# DummyLoad.net
KiCad netlist of a schematic drawn in EAGLE
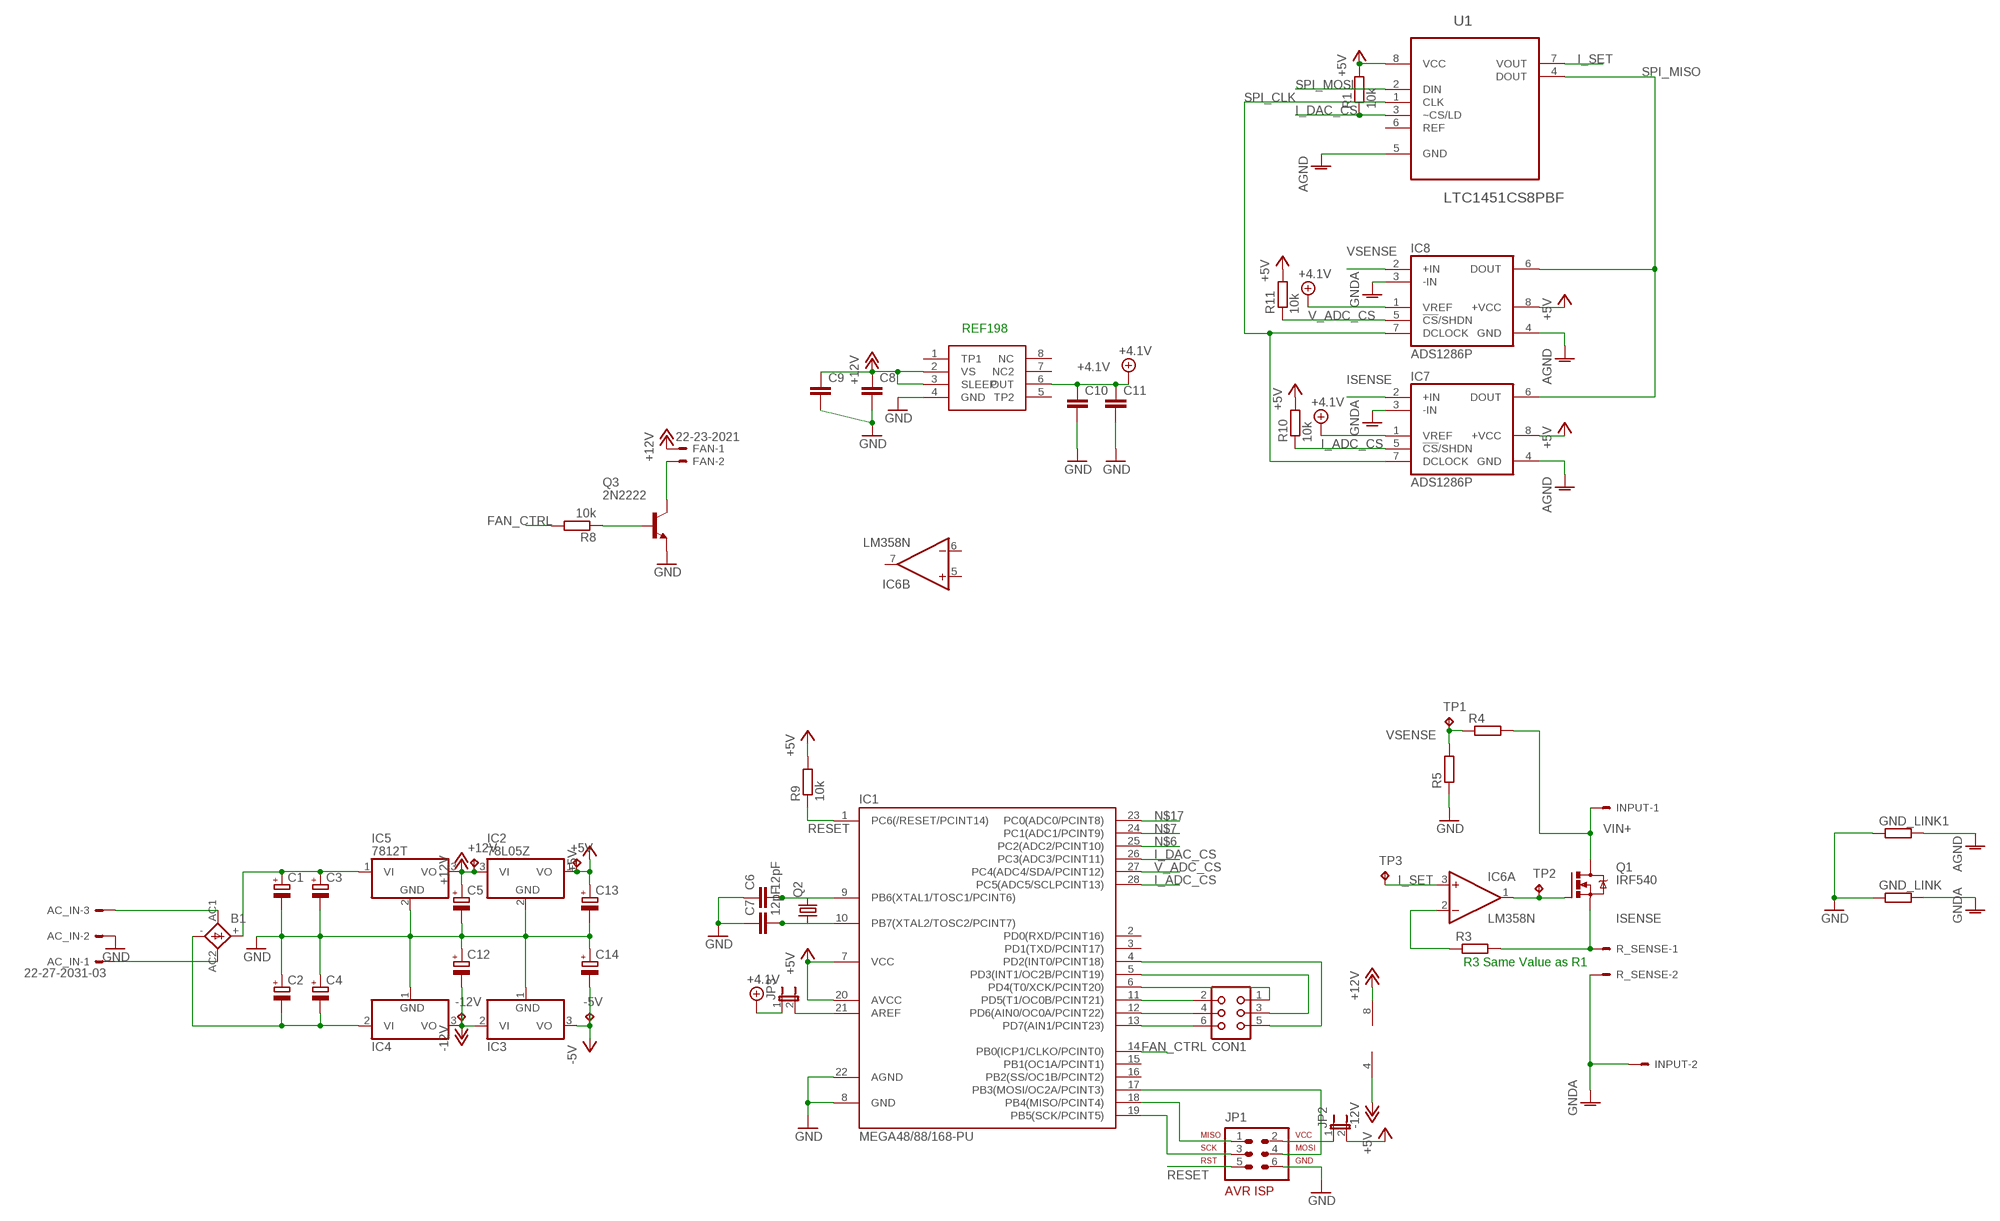
[diagram p0: schematic, sheet 1]

(export (version "E")
  (design (tool "Eeschema 10.0.6"))
  (components
    (comp (ref "+5V")
      (value "TPB2,54")
      (footprint "eagle-import:B2,54")
      (libsource (lib "eagle-import") (part "TPB2,54"))
    )
    (comp (ref "+12V")
      (value "TPB2,54")
      (footprint "eagle-import:B2,54")
      (libsource (lib "eagle-import") (part "TPB2,54"))
    )
    (comp (ref "-5V")
      (value "TPB2,54")
      (footprint "eagle-import:B2,54")
      (libsource (lib "eagle-import") (part "TPB2,54"))
    )
    (comp (ref "-12V")
      (value "TPB2,54")
      (footprint "eagle-import:B2,54")
      (libsource (lib "eagle-import") (part "TPB2,54"))
    )
    (comp (ref "AC_IN")
      (value "22-27-2031-03")
      (footprint "eagle-import:6410-03")
      (libsource (lib "eagle-import") (part "22-?-0327-2031"))
    )
    (comp (ref "B1")
      (value "2KBB-R")
      (footprint "eagle-import:2KBB-R")
      (libsource (lib "eagle-import") (part "2KBB-R"))
    )
    (comp (ref "C1")
      (value "CPOL-EUE5-8.5")
      (footprint "eagle-import:E5-8,5")
      (libsource (lib "eagle-import") (part "CPOL-EUE5-8.5"))
    )
    (comp (ref "C2")
      (value "CPOL-EUE5-8.5")
      (footprint "eagle-import:E5-8,5")
      (libsource (lib "eagle-import") (part "CPOL-EUE5-8.5"))
    )
    (comp (ref "C3")
      (value "CPOL-EUE5-8.5")
      (footprint "eagle-import:E5-8,5")
      (libsource (lib "eagle-import") (part "CPOL-EUE5-8.5"))
    )
    (comp (ref "C4")
      (value "CPOL-EUE5-8.5")
      (footprint "eagle-import:E5-8,5")
      (libsource (lib "eagle-import") (part "CPOL-EUE5-8.5"))
    )
    (comp (ref "C5")
      (value "CPOL-EUE2,5-6E")
      (footprint "eagle-import:E2,5-6E")
      (libsource (lib "eagle-import") (part "CPOL-EUE2,5-6E"))
    )
    (comp (ref "C6")
      (value "12pF")
      (footprint "eagle-import:C1206K")
      (libsource (lib "eagle-import") (part "C-EUC1206K"))
    )
    (comp (ref "C7")
      (value "12pF")
      (footprint "eagle-import:C1206K")
      (libsource (lib "eagle-import") (part "C-EUC1206K"))
    )
    (comp (ref "C8")
      (value "C-EUC1206K")
      (footprint "eagle-import:C1206K")
      (libsource (lib "eagle-import") (part "C-EUC1206K"))
    )
    (comp (ref "C9")
      (value "C-EUC1206K")
      (footprint "eagle-import:C1206K")
      (libsource (lib "eagle-import") (part "C-EUC1206K"))
    )
    (comp (ref "C10")
      (value "C-EUC1206K")
      (footprint "eagle-import:C1206K")
      (libsource (lib "eagle-import") (part "C-EUC1206K"))
    )
    (comp (ref "C11")
      (value "C-EUC1206K")
      (footprint "eagle-import:C1206K")
      (libsource (lib "eagle-import") (part "C-EUC1206K"))
    )
    (comp (ref "C12")
      (value "CPOL-EUE2,5-6E")
      (footprint "eagle-import:E2,5-6E")
      (libsource (lib "eagle-import") (part "CPOL-EUE2,5-6E"))
    )
    (comp (ref "C13")
      (value "CPOL-EUE2,5-6E")
      (footprint "eagle-import:E2,5-6E")
      (libsource (lib "eagle-import") (part "CPOL-EUE2,5-6E"))
    )
    (comp (ref "C14")
      (value "CPOL-EUE2,5-6E")
      (footprint "eagle-import:E2,5-6E")
      (libsource (lib "eagle-import") (part "CPOL-EUE2,5-6E"))
    )
    (comp (ref "CON1")
      (value "CON06")
      (footprint "eagle-import:CON06")
      (libsource (lib "eagle-import") (part "CON06"))
    )
    (comp (ref "FAN")
      (value "22-23-2021")
      (footprint "eagle-import:22-23-2021")
      (fields (field (name "MF") "MOLEX"))
      (libsource (lib "eagle-import") (part "22-23-2021"))
    )
    (comp (ref "GND_LINK")
      (value "R-EU_0204/2V")
      (footprint "eagle-import:0204V")
      (libsource (lib "eagle-import") (part "R-EU_0204/2V"))
    )
    (comp (ref "GND_LINK1")
      (value "R-EU_0204/2V")
      (footprint "eagle-import:0204V")
      (libsource (lib "eagle-import") (part "R-EU_0204/2V"))
    )
    (comp (ref "IC1")
      (value "MEGA48/88/168-PU")
      (footprint "eagle-import:DIL28-3")
      (libsource (lib "eagle-import") (part "MEGA48/88/168-PU"))
    )
    (comp (ref "IC2")
      (value "78L05Z")
      (footprint "eagle-import:TO92")
      (libsource (lib "eagle-import") (part "78ZL05"))
    )
    (comp (ref "IC3")
      (value "79L05Z")
      (footprint "eagle-import:TO92")
      (libsource (lib "eagle-import") (part "79ZL05"))
    )
    (comp (ref "IC4")
      (value "7912T")
      (footprint "eagle-import:TO220H")
      (libsource (lib "eagle-import") (part "79T12"))
    )
    (comp (ref "IC5")
      (value "7812T")
      (footprint "eagle-import:TO220H")
      (libsource (lib "eagle-import") (part "78T12"))
    )
    (comp (ref "IC6")
      (value "LM358N")
      (footprint "eagle-import:DIL08")
      (libsource (lib "eagle-import") (part "LM358N"))
    )
    (comp (ref "IC7")
      (value "ADS1286P")
      (footprint "eagle-import:DIL08")
      (fields (field (name "MF") "TEXAS INSTRUMENT CONNECTORS"))
      (libsource (lib "eagle-import") (part "ADS1286P"))
    )
    (comp (ref "IC8")
      (value "ADS1286P")
      (footprint "eagle-import:DIL08")
      (fields (field (name "MF") "TEXAS INSTRUMENT CONNECTORS"))
      (libsource (lib "eagle-import") (part "ADS1286P"))
    )
    (comp (ref "INPUT")
      (value "KK-156-2")
      (footprint "eagle-import:KK-156-2")
      (libsource (lib "eagle-import") (part "KK-156-2"))
    )
    (comp (ref "JP1")
      (value "AVR-ISP-6VERT")
      (footprint "eagle-import:AVR-ISP-6")
      (libsource (lib "eagle-import") (part "AVR-ISP-6VERT"))
    )
    (comp (ref "JP2")
      (value "JP1E")
      (footprint "eagle-import:JP1")
      (libsource (lib "eagle-import") (part "JP1E"))
    )
    (comp (ref "JP3")
      (value "JP1E")
      (footprint "eagle-import:JP1")
      (libsource (lib "eagle-import") (part "JP1E"))
    )
    (comp (ref "Q1")
      (value "IRF540")
      (footprint "eagle-import:TO220BV")
      (libsource (lib "eagle-import") (part "IRF540"))
    )
    (comp (ref "Q2")
      (value "CRYSTALHC18U-V")
      (footprint "eagle-import:HC18U-V")
      (libsource (lib "eagle-import") (part "CRYSTALHC18U-V"))
    )
    (comp (ref "Q3")
      (value "2N2222")
      (footprint "eagle-import:TO18")
      (libsource (lib "eagle-import") (part "2N2222"))
    )
    (comp (ref "R1")
      (value "10k")
      (footprint "eagle-import:M1206")
      (libsource (lib "eagle-import") (part "R-EU_M1206"))
    )
    (comp (ref "R3")
      (value "R-EU_M1206")
      (footprint "eagle-import:M1206")
      (libsource (lib "eagle-import") (part "R-EU_M1206"))
    )
    (comp (ref "R4")
      (value "R-EU_M1206")
      (footprint "eagle-import:M1206")
      (libsource (lib "eagle-import") (part "R-EU_M1206"))
    )
    (comp (ref "R5")
      (value "R-EU_M1206")
      (footprint "eagle-import:M1206")
      (libsource (lib "eagle-import") (part "R-EU_M1206"))
    )
    (comp (ref "R8")
      (value "10k")
      (footprint "eagle-import:0204_7")
      (libsource (lib "eagle-import") (part "R-EU_0204/7"))
    )
    (comp (ref "R9")
      (value "10k")
      (footprint "eagle-import:M1206")
      (libsource (lib "eagle-import") (part "R-EU_M1206"))
    )
    (comp (ref "R10")
      (value "10k")
      (footprint "eagle-import:M1206")
      (libsource (lib "eagle-import") (part "R-EU_M1206"))
    )
    (comp (ref "R11")
      (value "10k")
      (footprint "eagle-import:M1206")
      (libsource (lib "eagle-import") (part "R-EU_M1206"))
    )
    (comp (ref "R_SENSE")
      (value "KK-156-2")
      (footprint "eagle-import:KK-156-2")
      (libsource (lib "eagle-import") (part "KK-156-2"))
    )
    (comp (ref "TP1")
      (value "TPB2,54")
      (footprint "eagle-import:B2,54")
      (libsource (lib "eagle-import") (part "TPB2,54"))
    )
    (comp (ref "TP2")
      (value "TPB2,54")
      (footprint "eagle-import:B2,54")
      (libsource (lib "eagle-import") (part "TPB2,54"))
    )
    (comp (ref "TP3")
      (value "TPB2,54")
      (footprint "eagle-import:B2,54")
      (libsource (lib "eagle-import") (part "TPB2,54"))
    )
    (comp (ref "U$1")
      (value "REF195")
      (footprint "eagle-import:DIL08")
      (libsource (lib "eagle-import") (part "REF195"))
    )
    (comp (ref "U1")
      (value "LTC1451CS8PBF")
      (footprint "eagle-import:SOIC127P600X175-8N")
      (fields (field (name "MPN") "LTC1451CS8#PBF"))
      (libsource (lib "eagle-import") (part "LTC1451CS8PBF"))
    )
  )
  (nets
    (net (code "1") (name "+4.1V") (class "Default")
      (node (ref "C10") (pin "1") (pinfunction "1_1") (pintype "passive"))
      (node (ref "C11") (pin "1") (pinfunction "1_1") (pintype "passive"))
      (node (ref "IC7") (pin "1") (pinfunction "VREF_1") (pintype "input"))
      (node (ref "IC8") (pin "1") (pinfunction "VREF_1") (pintype "input"))
      (node (ref "JP3") (pin "1") (pinfunction "1_1") (pintype "passive"))
      (node (ref "U$1") (pin "6") (pinfunction "OUT_6") (pintype "bidirectional"))
    )
    (net (code "2") (name "+5V") (class "Default")
      (node (ref "+5V") (pin "TP") (pinfunction "TP_TP") (pintype "input"))
      (node (ref "C13") (pin "+") (pinfunction "+_+") (pintype "passive"))
      (node (ref "IC1") (pin "20") (pinfunction "AVCC_20") (pintype "passive"))
      (node (ref "IC1") (pin "7") (pinfunction "VCC_7") (pintype "power_in"))
      (node (ref "IC2") (pin "1") (pinfunction "VO_1") (pintype "passive"))
      (node (ref "IC7") (pin "8") (pinfunction "+VCC_8") (pintype "power_in"))
      (node (ref "IC8") (pin "8") (pinfunction "+VCC_8") (pintype "power_in"))
      (node (ref "JP2") (pin "2") (pinfunction "2_2") (pintype "passive"))
      (node (ref "R1") (pin "2") (pinfunction "2_2") (pintype "passive"))
      (node (ref "R10") (pin "2") (pinfunction "2_2") (pintype "passive"))
      (node (ref "R11") (pin "2") (pinfunction "2_2") (pintype "passive"))
      (node (ref "R9") (pin "2") (pinfunction "2_2") (pintype "passive"))
      (node (ref "U1") (pin "8") (pinfunction "VCC_8") (pintype "power_in"))
    )
    (net (code "3") (name "+12V") (class "Default")
      (node (ref "+12V") (pin "TP") (pinfunction "TP_TP") (pintype "input"))
      (node (ref "C5") (pin "+") (pinfunction "+_+") (pintype "passive"))
      (node (ref "C8") (pin "1") (pinfunction "1_1") (pintype "passive"))
      (node (ref "C9") (pin "1") (pinfunction "1_1") (pintype "passive"))
      (node (ref "FAN") (pin "1") (pinfunction "S_1") (pintype "passive"))
      (node (ref "IC2") (pin "3") (pinfunction "VI_3") (pintype "input"))
      (node (ref "IC5") (pin "3") (pinfunction "VO_3") (pintype "passive"))
      (node (ref "IC6") (pin "8") (pinfunction "V+_8") (pintype "power_in"))
      (node (ref "U$1") (pin "2") (pinfunction "VS_2") (pintype "power_in"))
      (node (ref "U$1") (pin "3") (pinfunction "SLEEP_3") (pintype "bidirectional"))
    )
    (net (code "4") (name "-5V") (class "Default")
      (node (ref "-5V") (pin "TP") (pinfunction "TP_TP") (pintype "input"))
      (node (ref "C14") (pin "-") (pinfunction "-_-") (pintype "passive"))
      (node (ref "IC3") (pin "3") (pinfunction "VO_3") (pintype "passive"))
    )
    (net (code "5") (name "-12V") (class "Default")
      (node (ref "-12V") (pin "TP") (pinfunction "TP_TP") (pintype "input"))
      (node (ref "C12") (pin "-") (pinfunction "-_-") (pintype "passive"))
      (node (ref "IC3") (pin "2") (pinfunction "VI_2") (pintype "input"))
      (node (ref "IC4") (pin "3") (pinfunction "VO_3") (pintype "passive"))
      (node (ref "IC6") (pin "4") (pinfunction "V-_4") (pintype "power_in"))
    )
    (net (code "6") (name "/FAN_CTRL") (class "Default")
      (node (ref "IC1") (pin "14") (pinfunction "PB0(ICP1/CLKO/PCINT0)_14") (pintype "bidirectional"))
      (node (ref "R8") (pin "2") (pinfunction "2_2") (pintype "passive"))
    )
    (net (code "7") (name "/ISENSE") (class "Default")
      (node (ref "IC7") (pin "2") (pinfunction "+IN_2") (pintype "input"))
      (node (ref "Q1") (pin "S") (pinfunction "S_S") (pintype "passive"))
      (node (ref "R3") (pin "2") (pinfunction "2_2") (pintype "passive"))
      (node (ref "R_SENSE") (pin "1") (pinfunction "S_1") (pintype "passive"))
    )
    (net (code "8") (name "/I_ADC_CS") (class "Default")
      (node (ref "IC1") (pin "28") (pinfunction "PC5(ADC5/SCLPCINT13)_28") (pintype "bidirectional"))
      (node (ref "IC7") (pin "5") (pinfunction "~{CS}/SHDN_5") (pintype "input"))
      (node (ref "R10") (pin "1") (pinfunction "1_1") (pintype "passive"))
    )
    (net (code "9") (name "/I_DAC_CS") (class "Default")
      (node (ref "IC1") (pin "26") (pinfunction "PC3(ADC3/PCINT11)_26") (pintype "bidirectional"))
      (node (ref "R1") (pin "1") (pinfunction "1_1") (pintype "passive"))
      (node (ref "U1") (pin "3") (pinfunction "~{CS/LD}_3") (pintype "input"))
    )
    (net (code "10") (name "/I_SET") (class "Default")
      (node (ref "IC6") (pin "3") (pinfunction "+IN_3") (pintype "input"))
      (node (ref "TP3") (pin "TP") (pinfunction "TP_TP") (pintype "input"))
      (node (ref "U1") (pin "7") (pinfunction "VOUT_7") (pintype "output"))
    )
    (net (code "11") (name "/N$6") (class "Default")
      (node (ref "IC1") (pin "25") (pinfunction "PC2(ADC2/PCINT10)_25") (pintype "bidirectional"))
    )
    (net (code "12") (name "/N$7") (class "Default")
      (node (ref "IC1") (pin "24") (pinfunction "PC1(ADC1/PCINT9)_24") (pintype "bidirectional"))
    )
    (net (code "13") (name "/N$17") (class "Default")
      (node (ref "IC1") (pin "23") (pinfunction "PC0(ADC0/PCINT8)_23") (pintype "bidirectional"))
    )
    (net (code "14") (name "/RESET") (class "Default")
      (node (ref "IC1") (pin "1") (pinfunction "PC6(/RESET/PCINT14)_1") (pintype "bidirectional"))
      (node (ref "JP1") (pin "5") (pinfunction "5_5") (pintype "passive"))
      (node (ref "R9") (pin "1") (pinfunction "1_1") (pintype "passive"))
    )
    (net (code "15") (name "/SPI_CLK") (class "Default")
      (node (ref "IC1") (pin "19") (pinfunction "PB5(SCK/PCINT5)_19") (pintype "bidirectional"))
      (node (ref "IC7") (pin "7") (pinfunction "DCLOCK_7") (pintype "input"))
      (node (ref "IC8") (pin "7") (pinfunction "DCLOCK_7") (pintype "input"))
      (node (ref "JP1") (pin "3") (pinfunction "3_3") (pintype "passive"))
      (node (ref "U1") (pin "1") (pinfunction "CLK_1") (pintype "input"))
    )
    (net (code "16") (name "/SPI_MISO") (class "Default")
      (node (ref "IC1") (pin "18") (pinfunction "PB4(MISO/PCINT4)_18") (pintype "bidirectional"))
      (node (ref "IC7") (pin "6") (pinfunction "DOUT_6") (pintype "output"))
      (node (ref "IC8") (pin "6") (pinfunction "DOUT_6") (pintype "output"))
      (node (ref "JP1") (pin "1") (pinfunction "1_1") (pintype "passive"))
      (node (ref "U1") (pin "4") (pinfunction "DOUT_4") (pintype "output"))
    )
    (net (code "17") (name "/SPI_MOSI") (class "Default")
      (node (ref "IC1") (pin "17") (pinfunction "PB3(MOSI/OC2A/PCINT3)_17") (pintype "bidirectional"))
      (node (ref "JP1") (pin "4") (pinfunction "4_4") (pintype "passive"))
      (node (ref "U1") (pin "2") (pinfunction "DIN_2") (pintype "input"))
    )
    (net (code "18") (name "/VIN+") (class "Default")
      (node (ref "INPUT") (pin "1") (pinfunction "S_1") (pintype "passive"))
      (node (ref "Q1") (pin "D") (pinfunction "D_D") (pintype "passive"))
      (node (ref "R4") (pin "2") (pinfunction "2_2") (pintype "passive"))
    )
    (net (code "19") (name "/VSENSE") (class "Default")
      (node (ref "IC8") (pin "2") (pinfunction "+IN_2") (pintype "input"))
      (node (ref "R4") (pin "1") (pinfunction "1_1") (pintype "passive"))
      (node (ref "R5") (pin "2") (pinfunction "2_2") (pintype "passive"))
      (node (ref "TP1") (pin "TP") (pinfunction "TP_TP") (pintype "input"))
    )
    (net (code "20") (name "/V_ADC_CS") (class "Default")
      (node (ref "IC1") (pin "27") (pinfunction "PC4(ADC4/SDA/PCINT12)_27") (pintype "bidirectional"))
      (node (ref "IC8") (pin "5") (pinfunction "~{CS}/SHDN_5") (pintype "input"))
      (node (ref "R11") (pin "1") (pinfunction "1_1") (pintype "passive"))
    )
    (net (code "21") (name "AGND") (class "Default")
      (node (ref "GND_LINK1") (pin "2") (pinfunction "2_2") (pintype "passive"))
      (node (ref "IC7") (pin "4") (pinfunction "GND_4") (pintype "power_in"))
      (node (ref "IC8") (pin "4") (pinfunction "GND_4") (pintype "power_in"))
      (node (ref "U1") (pin "5") (pinfunction "GND_5") (pintype "passive"))
    )
    (net (code "22") (name "GND") (class "Default")
      (node (ref "AC_IN") (pin "2") (pinfunction "S_2") (pintype "passive"))
      (node (ref "C1") (pin "-") (pinfunction "-_-") (pintype "passive"))
      (node (ref "C10") (pin "2") (pinfunction "2_2") (pintype "passive"))
      (node (ref "C11") (pin "2") (pinfunction "2_2") (pintype "passive"))
      (node (ref "C12") (pin "+") (pinfunction "+_+") (pintype "passive"))
      (node (ref "C13") (pin "-") (pinfunction "-_-") (pintype "passive"))
      (node (ref "C14") (pin "+") (pinfunction "+_+") (pintype "passive"))
      (node (ref "C2") (pin "+") (pinfunction "+_+") (pintype "passive"))
      (node (ref "C3") (pin "-") (pinfunction "-_-") (pintype "passive"))
      (node (ref "C4") (pin "+") (pinfunction "+_+") (pintype "passive"))
      (node (ref "C5") (pin "-") (pinfunction "-_-") (pintype "passive"))
      (node (ref "C6") (pin "1") (pinfunction "1_1") (pintype "passive"))
      (node (ref "C7") (pin "1") (pinfunction "1_1") (pintype "passive"))
      (node (ref "C8") (pin "2") (pinfunction "2_2") (pintype "passive"))
      (node (ref "C9") (pin "2") (pinfunction "2_2") (pintype "passive"))
      (node (ref "GND_LINK") (pin "1") (pinfunction "1_1") (pintype "passive"))
      (node (ref "GND_LINK1") (pin "1") (pinfunction "1_1") (pintype "passive"))
      (node (ref "IC1") (pin "22") (pinfunction "AGND_22") (pintype "power_in"))
      (node (ref "IC1") (pin "8") (pinfunction "GND_8") (pintype "power_in"))
      (node (ref "IC2") (pin "2") (pinfunction "GND_2") (pintype "passive"))
      (node (ref "IC3") (pin "1") (pinfunction "GND_1") (pintype "passive"))
      (node (ref "IC4") (pin "1") (pinfunction "GND_1") (pintype "passive"))
      (node (ref "IC5") (pin "2") (pinfunction "GND_2") (pintype "passive"))
      (node (ref "JP1") (pin "6") (pinfunction "6_6") (pintype "passive"))
      (node (ref "Q3") (pin "1") (pinfunction "E_1") (pintype "passive"))
      (node (ref "R5") (pin "1") (pinfunction "1_1") (pintype "passive"))
      (node (ref "U$1") (pin "4") (pinfunction "GND_4") (pintype "power_in"))
    )
    (net (code "23") (name "GNDA") (class "Default")
      (node (ref "GND_LINK") (pin "2") (pinfunction "2_2") (pintype "passive"))
      (node (ref "IC7") (pin "3") (pinfunction "-IN_3") (pintype "input"))
      (node (ref "IC8") (pin "3") (pinfunction "-IN_3") (pintype "input"))
      (node (ref "INPUT") (pin "2") (pinfunction "S_2") (pintype "passive"))
      (node (ref "R_SENSE") (pin "2") (pinfunction "S_2") (pintype "passive"))
    )
    (net (code "24") (name "Net-(AC_INA-S)") (class "Default")
      (node (ref "AC_IN") (pin "1") (pinfunction "S_1") (pintype "passive"))
      (node (ref "B1") (pin "AC2") (pinfunction "AC2_AC2") (pintype "passive"))
    )
    (net (code "25") (name "Net-(AC_INC-S)") (class "Default")
      (node (ref "AC_IN") (pin "3") (pinfunction "S_3") (pintype "passive"))
      (node (ref "B1") (pin "AC1") (pinfunction "AC1_AC1") (pintype "passive"))
    )
    (net (code "26") (name "Net-(FANB-S)") (class "Default")
      (node (ref "FAN") (pin "2") (pinfunction "S_2") (pintype "passive"))
      (node (ref "Q3") (pin "3") (pinfunction "C_3") (pintype "passive"))
    )
    (net (code "27") (name "Net-(IC1-AREF)") (class "Default")
      (node (ref "IC1") (pin "21") (pinfunction "AREF_21") (pintype "passive"))
      (node (ref "JP3") (pin "2") (pinfunction "2_2") (pintype "passive"))
    )
    (net (code "28") (name "Net-(IC1-PB6(XTAL1{slash}TOSC1{slash}PCINT6))") (class "Default")
      (node (ref "C6") (pin "2") (pinfunction "2_2") (pintype "passive"))
      (node (ref "IC1") (pin "9") (pinfunction "PB6(XTAL1/TOSC1/PCINT6)_9") (pintype "bidirectional"))
      (node (ref "Q2") (pin "2") (pinfunction "2_2") (pintype "passive"))
    )
    (net (code "29") (name "Net-(IC1-PB7(XTAL2{slash}TOSC2{slash}PCINT7))") (class "Default")
      (node (ref "C7") (pin "2") (pinfunction "2_2") (pintype "passive"))
      (node (ref "IC1") (pin "10") (pinfunction "PB7(XTAL2/TOSC2/PCINT7)_10") (pintype "bidirectional"))
      (node (ref "Q2") (pin "1") (pinfunction "1_1") (pintype "passive"))
    )
    (net (code "30") (name "Net-(IC1-PD2(INT0{slash}PCINT18))") (class "Default")
      (node (ref "CON1") (pin "5") (pinfunction "5_5") (pintype "passive"))
      (node (ref "IC1") (pin "4") (pinfunction "PD2(INT0/PCINT18)_4") (pintype "bidirectional"))
    )
    (net (code "31") (name "Net-(IC1-PD3(INT1{slash}OC2B{slash}PCINT19))") (class "Default")
      (node (ref "CON1") (pin "3") (pinfunction "3_3") (pintype "passive"))
      (node (ref "IC1") (pin "5") (pinfunction "PD3(INT1/OC2B/PCINT19)_5") (pintype "bidirectional"))
    )
    (net (code "32") (name "Net-(IC1-PD4(T0{slash}XCK{slash}PCINT20))") (class "Default")
      (node (ref "CON1") (pin "1") (pinfunction "1_1") (pintype "passive"))
      (node (ref "IC1") (pin "6") (pinfunction "PD4(T0/XCK/PCINT20)_6") (pintype "bidirectional"))
    )
    (net (code "33") (name "Net-(IC1-PD5(T1{slash}OC0B{slash}PCINT21))") (class "Default")
      (node (ref "CON1") (pin "2") (pinfunction "2_2") (pintype "passive"))
      (node (ref "IC1") (pin "11") (pinfunction "PD5(T1/OC0B/PCINT21)_11") (pintype "bidirectional"))
    )
    (net (code "34") (name "Net-(IC1-PD6(AIN0{slash}OC0A{slash}PCINT22))") (class "Default")
      (node (ref "CON1") (pin "4") (pinfunction "4_4") (pintype "passive"))
      (node (ref "IC1") (pin "12") (pinfunction "PD6(AIN0/OC0A/PCINT22)_12") (pintype "bidirectional"))
    )
    (net (code "35") (name "Net-(IC1-PD7(AIN1{slash}PCINT23))") (class "Default")
      (node (ref "CON1") (pin "6") (pinfunction "6_6") (pintype "passive"))
      (node (ref "IC1") (pin "13") (pinfunction "PD7(AIN1/PCINT23)_13") (pintype "bidirectional"))
    )
    (net (code "36") (name "Net-(IC4-VI)") (class "Default")
      (node (ref "B1") (pin "-") (pinfunction "-_-") (pintype "passive"))
      (node (ref "C2") (pin "-") (pinfunction "-_-") (pintype "passive"))
      (node (ref "C4") (pin "-") (pinfunction "-_-") (pintype "passive"))
      (node (ref "IC4") (pin "2") (pinfunction "VI_2") (pintype "input"))
    )
    (net (code "37") (name "Net-(IC5-VI)") (class "Default")
      (node (ref "B1") (pin "+") (pinfunction "+_+") (pintype "passive"))
      (node (ref "C1") (pin "+") (pinfunction "+_+") (pintype "passive"))
      (node (ref "C3") (pin "+") (pinfunction "+_+") (pintype "passive"))
      (node (ref "IC5") (pin "1") (pinfunction "VI_1") (pintype "input"))
    )
    (net (code "38") (name "Net-(IC6A--IN)") (class "Default")
      (node (ref "IC6") (pin "2") (pinfunction "-IN_2") (pintype "input"))
      (node (ref "R3") (pin "1") (pinfunction "1_1") (pintype "passive"))
    )
    (net (code "39") (name "Net-(IC6A-OUT)") (class "Default")
      (node (ref "IC6") (pin "1") (pinfunction "OUT_1") (pintype "output"))
      (node (ref "Q1") (pin "G") (pinfunction "G_G") (pintype "passive"))
      (node (ref "TP2") (pin "TP") (pinfunction "TP_TP") (pintype "input"))
    )
    (net (code "40") (name "Net-(JP1-Pad2)") (class "Default")
      (node (ref "JP1") (pin "2") (pinfunction "2_2") (pintype "passive"))
      (node (ref "JP2") (pin "1") (pinfunction "1_1") (pintype "passive"))
    )
    (net (code "41") (name "Net-(Q3-B)") (class "Default")
      (node (ref "Q3") (pin "2") (pinfunction "B_2") (pintype "passive"))
      (node (ref "R8") (pin "1") (pinfunction "1_1") (pintype "passive"))
    )
    (net (code "42") (name "unconnected-(IC1-PB1(OC1A{slash}PCINT1)-Pad15)") (class "Default")
      (node (ref "IC1") (pin "15") (pinfunction "PB1(OC1A/PCINT1)_15") (pintype "bidirectional"))
    )
    (net (code "43") (name "unconnected-(IC1-PB2(SS{slash}OC1B{slash}PCINT2)-Pad16)") (class "Default")
      (node (ref "IC1") (pin "16") (pinfunction "PB2(SS/OC1B/PCINT2)_16") (pintype "bidirectional"))
    )
    (net (code "44") (name "unconnected-(IC1-PD0(RXD{slash}PCINT16)-Pad2)") (class "Default")
      (node (ref "IC1") (pin "2") (pinfunction "PD0(RXD/PCINT16)_2") (pintype "bidirectional"))
    )
    (net (code "45") (name "unconnected-(IC1-PD1(TXD{slash}PCINT17)-Pad3)") (class "Default")
      (node (ref "IC1") (pin "3") (pinfunction "PD1(TXD/PCINT17)_3") (pintype "bidirectional"))
    )
    (net (code "46") (name "unconnected-(IC6B-+IN-Pad5)") (class "Default")
      (node (ref "IC6") (pin "5") (pinfunction "+IN_5") (pintype "input"))
    )
    (net (code "47") (name "unconnected-(IC6B--IN-Pad6)") (class "Default")
      (node (ref "IC6") (pin "6") (pinfunction "-IN_6") (pintype "input"))
    )
    (net (code "48") (name "unconnected-(IC6B-OUT-Pad7)") (class "Default")
      (node (ref "IC6") (pin "7") (pinfunction "OUT_7") (pintype "output"))
    )
    (net (code "49") (name "unconnected-(U$1-NC-Pad8)") (class "Default")
      (node (ref "U$1") (pin "8") (pinfunction "NC_8") (pintype "no_connect"))
    )
    (net (code "50") (name "unconnected-(U$1-NC2-Pad7)") (class "Default")
      (node (ref "U$1") (pin "7") (pinfunction "NC2_7") (pintype "no_connect"))
    )
    (net (code "51") (name "unconnected-(U$1-TP1-Pad1)") (class "Default")
      (node (ref "U$1") (pin "1") (pinfunction "TP1_1") (pintype "no_connect"))
    )
    (net (code "52") (name "unconnected-(U$1-TP2-Pad5)") (class "Default")
      (node (ref "U$1") (pin "5") (pinfunction "TP2_5") (pintype "no_connect"))
    )
    (net (code "53") (name "unconnected-(U1-REF-Pad6)") (class "Default")
      (node (ref "U1") (pin "6") (pinfunction "REF_6") (pintype "input"))
    )
  )
)
